# TIDA-01576_ADS8686S_AFE_Pg5-Voltage_Meas.net
KiCad netlist of a schematic drawn in Altium Designer
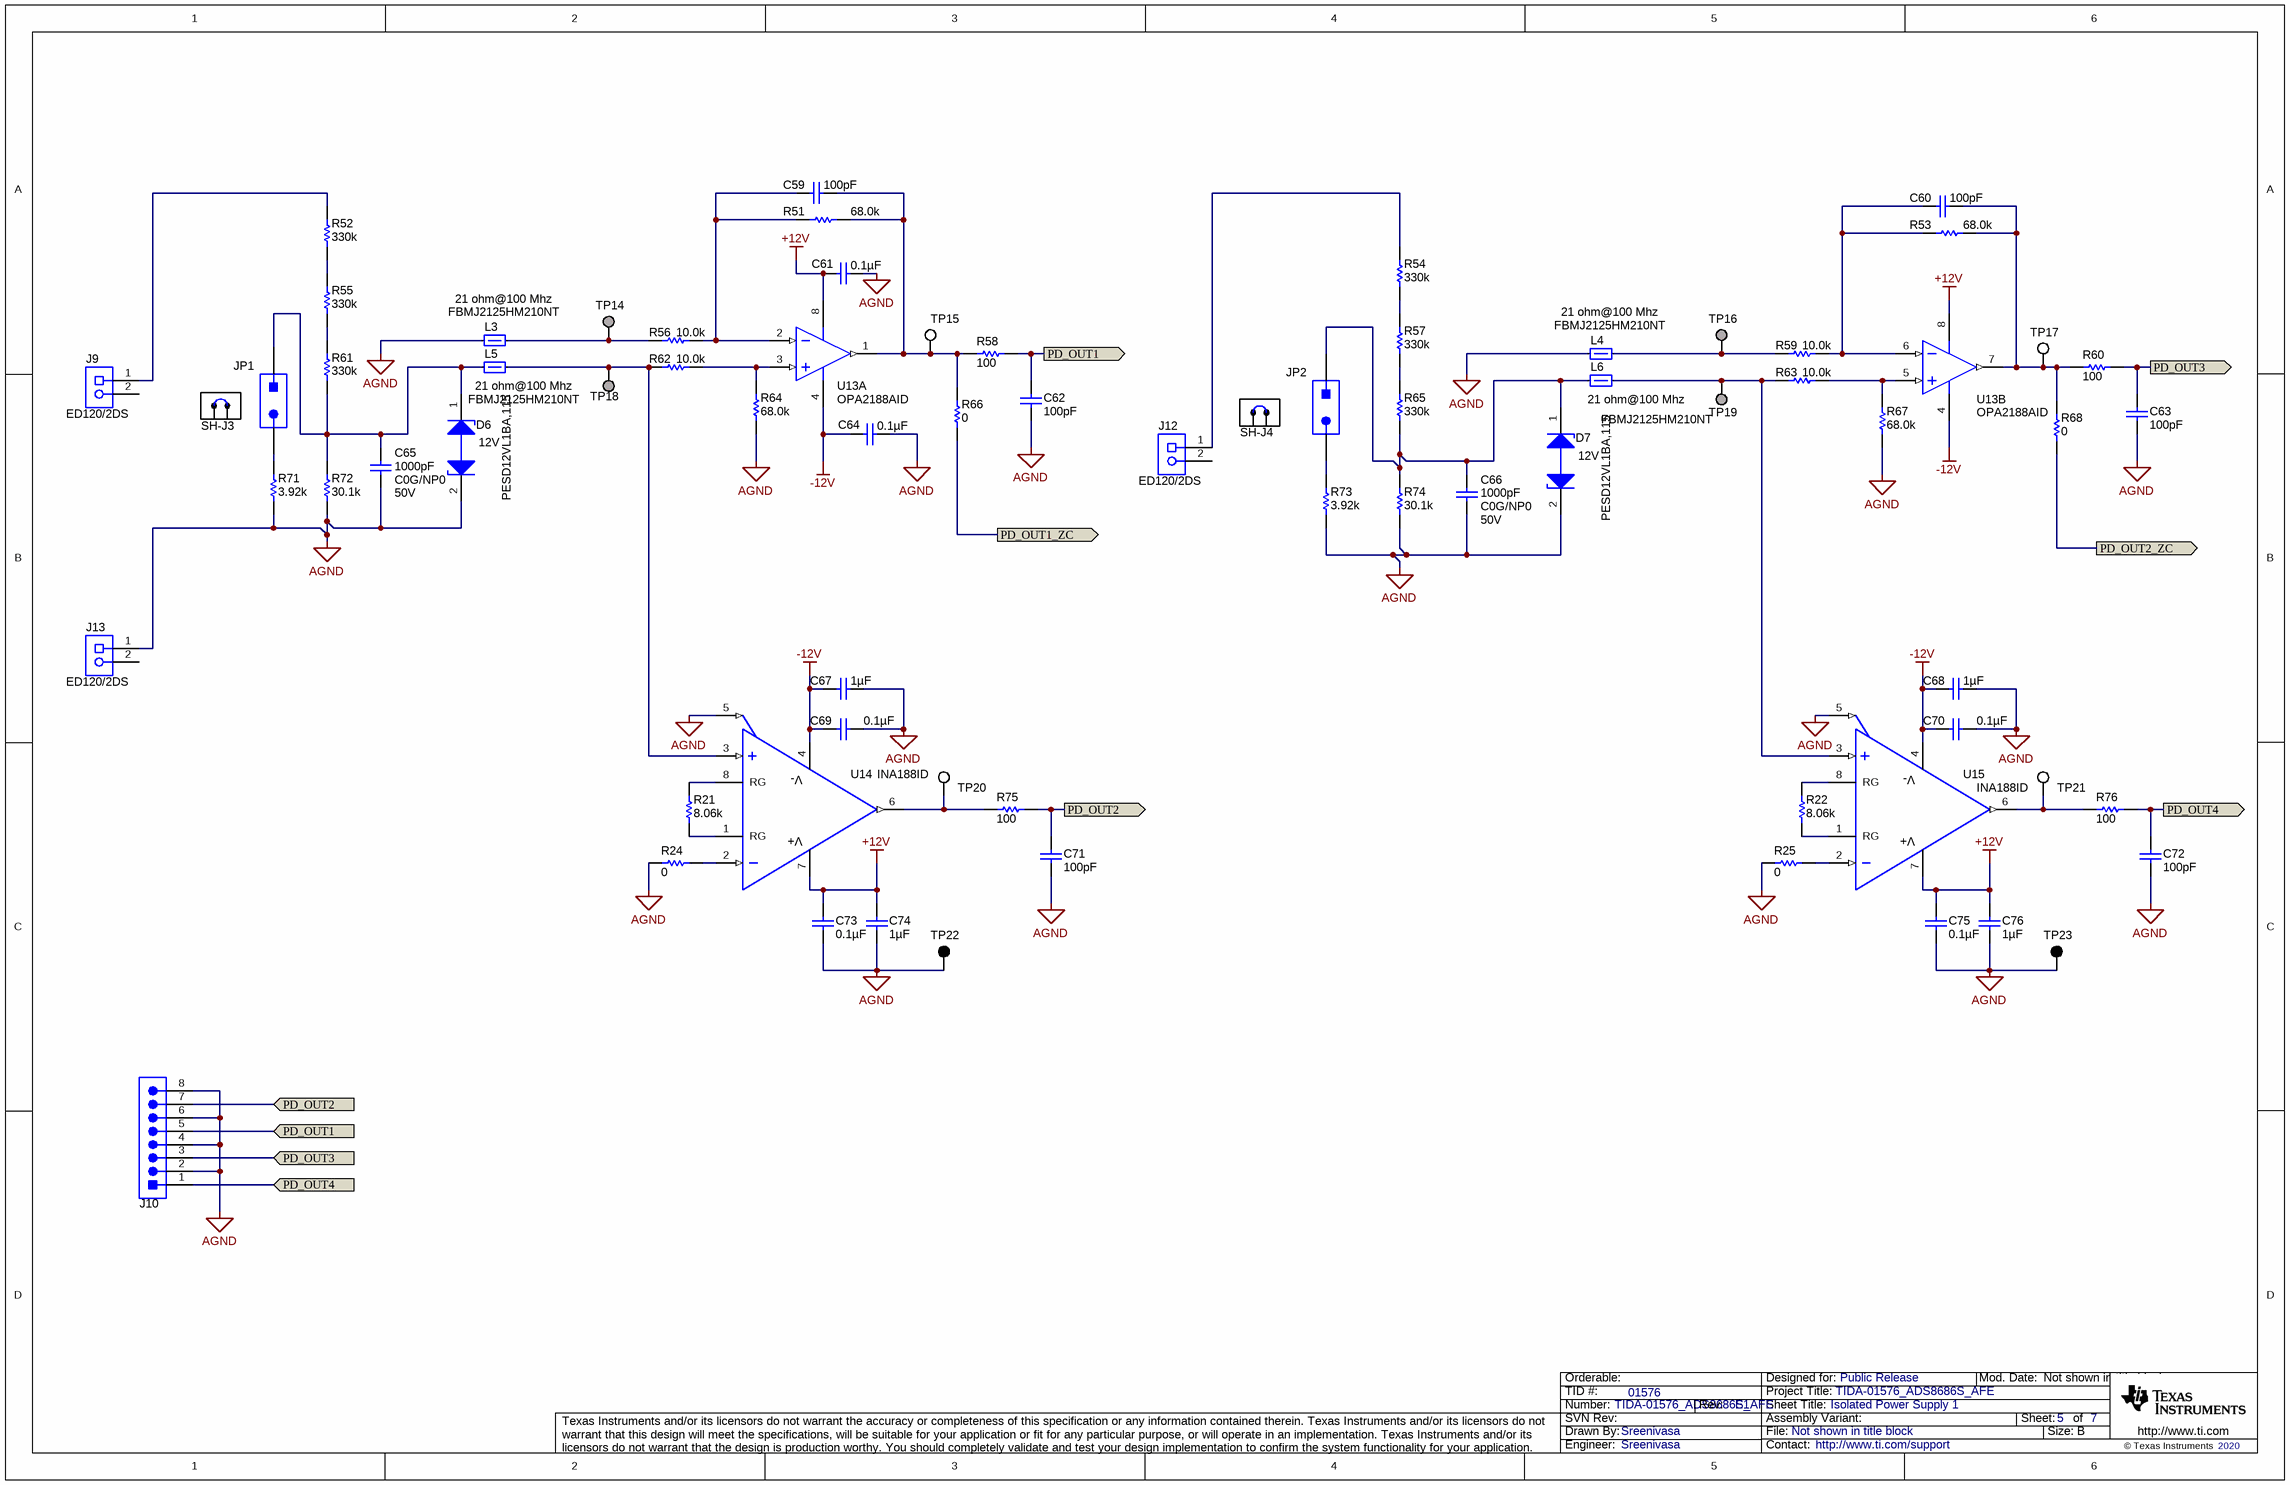
[diagram p0: TIDA-01576_ADS8686S_AFE_Pg5-Voltage Measurement.SchDoc]

(export (version "E")
  (design (tool "Eeschema 10.0.6"))
  (components
    (comp (ref "C59")
      (value "06033C101KAT2A")
      (footprint "0603")
      (description "CAP, CERM, 100pF, 25V, +/-10%, X7R, 0603")
      (fields
        (field (name "VALUEDISPLAYED") "100pF")
        (field (name "MANUFACTURER") "AVX")
        (field (name "PUBLISHER") "Texas Instruments")
      )
      (libsource (lib "Capacitor_Ceramic") (part "06033C101KAT2A"))
    )
    (comp (ref "C60")
      (value "06033C101KAT2A")
      (footprint "0603")
      (description "CAP, CERM, 100pF, 25V, +/-10%, X7R, 0603")
      (fields
        (field (name "VALUEDISPLAYED") "100pF")
        (field (name "MANUFACTURER") "AVX")
        (field (name "PUBLISHER") "Texas Instruments")
      )
      (libsource (lib "Capacitor_Ceramic") (part "06033C101KAT2A"))
    )
    (comp (ref "C61")
      (value "06033C104JAT2A")
      (footprint "0603")
      (description "CAP, CERM, 0.1uF, 25V, +/-5%, X7R, 0603")
      (fields
        (field (name "VALUEDISPLAYED") "0.1µF")
        (field (name "MANUFACTURER") "AVX")
        (field (name "PUBLISHER") "Texas Instruments")
      )
      (libsource (lib "Capacitor_Ceramic") (part "06033C104JAT2A"))
    )
    (comp (ref "C62")
      (value "06033C101KAT2A")
      (footprint "0603")
      (description "CAP, CERM, 100pF, 25V, +/-10%, X7R, 0603")
      (fields
        (field (name "VALUEDISPLAYED") "100pF")
        (field (name "MANUFACTURER") "AVX")
        (field (name "PUBLISHER") "Texas Instruments")
      )
      (libsource (lib "Capacitor_Ceramic") (part "06033C101KAT2A"))
    )
    (comp (ref "C63")
      (value "06033C101KAT2A")
      (footprint "0603")
      (description "CAP, CERM, 100pF, 25V, +/-10%, X7R, 0603")
      (fields
        (field (name "VALUEDISPLAYED") "100pF")
        (field (name "MANUFACTURER") "AVX")
        (field (name "PUBLISHER") "Texas Instruments")
      )
      (libsource (lib "Capacitor_Ceramic") (part "06033C101KAT2A"))
    )
    (comp (ref "C64")
      (value "06033C104JAT2A")
      (footprint "0603")
      (description "CAP, CERM, 0.1uF, 25V, +/-5%, X7R, 0603")
      (fields
        (field (name "VALUEDISPLAYED") "0.1µF")
        (field (name "MANUFACTURER") "AVX")
        (field (name "PUBLISHER") "Texas Instruments")
      )
      (libsource (lib "Capacitor_Ceramic") (part "06033C104JAT2A"))
    )
    (comp (ref "C65")
      (value "C1608C0G1H102J080AA")
      (footprint "0603")
      (description "CAP, CERM, 1000pF, 50V, +/-5%, C0G/NP0, 0603")
      (fields
        (field (name "VALUEDISPLAYED") "1000pF")
        (field (name "MANUFACTURER") "TDK")
        (field (name "VALUE2") "50V")
        (field (name "TEMPCO") "C0G/NP0")
        (field (name "PUBLISHER") "Texas Instruments")
      )
      (libsource (lib "Capacitor_Ceramic") (part "C1608C0G1H102J"))
    )
    (comp (ref "C66")
      (value "C1608C0G1H102J080AA")
      (footprint "0603")
      (description "CAP, CERM, 1000pF, 50V, +/-5%, C0G/NP0, 0603")
      (fields
        (field (name "VALUEDISPLAYED") "1000pF")
        (field (name "MANUFACTURER") "TDK")
        (field (name "VALUE2") "50V")
        (field (name "TEMPCO") "C0G/NP0")
        (field (name "PUBLISHER") "Texas Instruments")
      )
      (libsource (lib "Capacitor_Ceramic") (part "C1608C0G1H102J"))
    )
    (comp (ref "C67")
      (value "GRM188R61C105KA93D")
      (footprint "0603")
      (description "CAP, CERM, 1 µF, 16 V, +/- 10%, X5R, 0603")
      (fields
        (field (name "VALUEDISPLAYED") "1µF")
        (field (name "MANUFACTURER") "Murata")
        (field (name "PUBLISHER") "Texas Instruments")
      )
      (libsource (lib "Capacitor_Ceramic") (part "C1608X5R1C105K"))
    )
    (comp (ref "C68")
      (value "GRM188R61C105KA93D")
      (footprint "0603")
      (description "CAP, CERM, 1 µF, 16 V, +/- 10%, X5R, 0603")
      (fields
        (field (name "VALUEDISPLAYED") "1µF")
        (field (name "MANUFACTURER") "Murata")
        (field (name "PUBLISHER") "Texas Instruments")
      )
      (libsource (lib "Capacitor_Ceramic") (part "C1608X5R1C105K"))
    )
    (comp (ref "C69")
      (value "CGA3E2X8R1E104K080AA")
      (footprint "0603")
      (description "CAP, CERM, 0.1 µF, 25 V, +/- 10%, X8R, AEC-Q200 Grade 0, 0603")
      (fields
        (field (name "VALUEDISPLAYED") "0.1µF")
        (field (name "MANUFACTURER") "TDK")
        (field (name "PUBLISHER") "Texas Instruments")
      )
      (libsource (lib "Capacitor_Ceramic") (part "CGA3E2X8R1E104K080AA"))
    )
    (comp (ref "C70")
      (value "CGA3E2X8R1E104K080AA")
      (footprint "0603")
      (description "CAP, CERM, 0.1 µF, 25 V, +/- 10%, X8R, AEC-Q200 Grade 0, 0603")
      (fields
        (field (name "VALUEDISPLAYED") "0.1µF")
        (field (name "MANUFACTURER") "TDK")
        (field (name "PUBLISHER") "Texas Instruments")
      )
      (libsource (lib "Capacitor_Ceramic") (part "CGA3E2X8R1E104K080AA"))
    )
    (comp (ref "C71")
      (value "06033C101KAT2A")
      (footprint "0603")
      (description "CAP, CERM, 100pF, 25V, +/-10%, X7R, 0603")
      (fields
        (field (name "VALUEDISPLAYED") "100pF")
        (field (name "MANUFACTURER") "AVX")
        (field (name "PUBLISHER") "Texas Instruments")
      )
      (libsource (lib "Capacitor_Ceramic") (part "06033C101KAT2A"))
    )
    (comp (ref "C72")
      (value "06033C101KAT2A")
      (footprint "0603")
      (description "CAP, CERM, 100pF, 25V, +/-10%, X7R, 0603")
      (fields
        (field (name "VALUEDISPLAYED") "100pF")
        (field (name "MANUFACTURER") "AVX")
        (field (name "PUBLISHER") "Texas Instruments")
      )
      (libsource (lib "Capacitor_Ceramic") (part "06033C101KAT2A"))
    )
    (comp (ref "C73")
      (value "CGA3E2X8R1E104K080AA")
      (footprint "0603")
      (description "CAP, CERM, 0.1 µF, 25 V, +/- 10%, X8R, AEC-Q200 Grade 0, 0603")
      (fields
        (field (name "VALUEDISPLAYED") "0.1µF")
        (field (name "MANUFACTURER") "TDK")
        (field (name "PUBLISHER") "Texas Instruments")
      )
      (libsource (lib "Capacitor_Ceramic") (part "CGA3E2X8R1E104K080AA"))
    )
    (comp (ref "C74")
      (value "GRM188R61C105KA93D")
      (footprint "0603")
      (description "CAP, CERM, 1 µF, 16 V, +/- 10%, X5R, 0603")
      (fields
        (field (name "VALUEDISPLAYED") "1µF")
        (field (name "MANUFACTURER") "Murata")
        (field (name "PUBLISHER") "Texas Instruments")
      )
      (libsource (lib "Capacitor_Ceramic") (part "C1608X5R1C105K"))
    )
    (comp (ref "C75")
      (value "CGA3E2X8R1E104K080AA")
      (footprint "0603")
      (description "CAP, CERM, 0.1 µF, 25 V, +/- 10%, X8R, AEC-Q200 Grade 0, 0603")
      (fields
        (field (name "VALUEDISPLAYED") "0.1µF")
        (field (name "MANUFACTURER") "TDK")
        (field (name "PUBLISHER") "Texas Instruments")
      )
      (libsource (lib "Capacitor_Ceramic") (part "CGA3E2X8R1E104K080AA"))
    )
    (comp (ref "C76")
      (value "GRM188R61C105KA93D")
      (footprint "0603")
      (description "CAP, CERM, 1 µF, 16 V, +/- 10%, X5R, 0603")
      (fields
        (field (name "VALUEDISPLAYED") "1µF")
        (field (name "MANUFACTURER") "Murata")
        (field (name "PUBLISHER") "Texas Instruments")
      )
      (libsource (lib "Capacitor_Ceramic") (part "C1608X5R1C105K"))
    )
    (comp (ref "D6")
      (value "12V")
      (footprint "SOD-323")
      (description "TVS DIODE 12VWM 37VC SOD323")
      (fields
        (field (name "PARTNUMBER") "PESD12VL1BA,115")
        (field (name "MANUFACTURER") "NXP Semiconductor")
        (field (name "Comment") "PESD12VL1BA,115")
        (field (name "SYMBOLCREATOR") "x0199378")
      )
      (libsource (lib "PESD3V3L1BA") (part "PESD3V3L1BA"))
    )
    (comp (ref "D7")
      (value "12V")
      (footprint "SOD-323")
      (description "TVS DIODE 12VWM 37VC SOD323")
      (fields
        (field (name "PARTNUMBER") "PESD12VL1BA,115")
        (field (name "MANUFACTURER") "NXP Semiconductor")
        (field (name "Comment") "PESD12VL1BA,115")
        (field (name "SYMBOLCREATOR") "x0199378")
      )
      (libsource (lib "PESD3V3L1BA") (part "PESD3V3L1BA"))
    )
    (comp (ref "J9")
      (value "ED120/2DS")
      (footprint "CONN_ED120-2DS")
      (description "TERMINAL BLOCK 5.08MM VERT 2POS, TH")
      (fields
        (field (name "MANUFACTURER") "On-Shore Technology")
        (field (name "SYMBOLCREATOR") "a0412235")
        (field (name "PUBLISHER") "Texas Instruments")
      )
      (libsource (lib "Connectors") (part "ED120/2DS"))
    )
    (comp (ref "J10")
      (value "1803332")
      (footprint "Phoenix_1803332")
      (description "Header(shrouded), 3.81mm, 8x1, Tin, R/A, TH")
      (fields (field (name "MANUFACTURER") "Phoenix Contact"))
      (libsource (lib "Altium Vault - TI") (part "CMP-0078749-1"))
    )
    (comp (ref "J12")
      (value "ED120/2DS")
      (footprint "CONN_ED120-2DS")
      (description "TERMINAL BLOCK 5.08MM VERT 2POS, TH")
      (fields
        (field (name "MANUFACTURER") "On-Shore Technology")
        (field (name "SYMBOLCREATOR") "a0412235")
        (field (name "PUBLISHER") "Texas Instruments")
      )
      (libsource (lib "Connectors") (part "ED120/2DS"))
    )
    (comp (ref "J13")
      (value "ED120/2DS")
      (footprint "CONN_ED120-2DS")
      (description "TERMINAL BLOCK 5.08MM VERT 2POS, TH")
      (fields
        (field (name "MANUFACTURER") "On-Shore Technology")
        (field (name "SYMBOLCREATOR") "a0412235")
        (field (name "PUBLISHER") "Texas Instruments")
      )
      (libsource (lib "Connectors") (part "ED120/2DS"))
    )
    (comp (ref "JP1")
      (value "5-146280-2")
      (footprint "TSW-102-07-G-S")
      (description "Header, 100mil, 2x1, Gold, TH")
      (fields
        (field (name "MANUFACTURER") "TE Connectivity")
        (field (name "SYMBOLCREATOR") "a0412235")
        (field (name "PUBLISHER") "Texas Instruments")
      )
      (libsource (lib "Connectors_Samtec") (part "TSW-102-07-G-S"))
    )
    (comp (ref "JP2")
      (value "5-146280-2")
      (footprint "TSW-102-07-G-S")
      (description "Header, 100mil, 2x1, Gold, TH")
      (fields
        (field (name "MANUFACTURER") "TE Connectivity")
        (field (name "SYMBOLCREATOR") "a0412235")
        (field (name "PUBLISHER") "Texas Instruments")
      )
      (libsource (lib "Connectors_Samtec") (part "TSW-102-07-G-S"))
    )
    (comp (ref "L3")
      (value "21 ohm@100 Mhz")
      (footprint "0805_HV")
      (description "Ferrite Bead, 21 ohm @ 100 MHz, 6 A, 0805")
      (fields
        (field (name "PARTNUMBER") "FBMJ2125HM210NT")
        (field (name "MANUFACTURER") "Taiyo Yuden")
        (field (name "Comment") "FBMJ2125HM210NT")
        (field (name "PUBLISHER") "Texas Instruments")
      )
      (libsource (lib "FerriteBead") (part "FBMJ2125HM210NT"))
    )
    (comp (ref "L4")
      (value "21 ohm@100 Mhz")
      (footprint "0805_HV")
      (description "Ferrite Bead, 21 ohm @ 100 MHz, 6 A, 0805")
      (fields
        (field (name "PARTNUMBER") "FBMJ2125HM210NT")
        (field (name "MANUFACTURER") "Taiyo Yuden")
        (field (name "Comment") "FBMJ2125HM210NT")
        (field (name "PUBLISHER") "Texas Instruments")
      )
      (libsource (lib "FerriteBead") (part "FBMJ2125HM210NT"))
    )
    (comp (ref "L5")
      (value "21 ohm@100 Mhz")
      (footprint "0805_HV")
      (description "Ferrite Bead, 21 ohm @ 100 MHz, 6 A, 0805")
      (fields
        (field (name "PARTNUMBER") "FBMJ2125HM210NT")
        (field (name "MANUFACTURER") "Taiyo Yuden")
        (field (name "Comment") "FBMJ2125HM210NT")
        (field (name "PUBLISHER") "Texas Instruments")
      )
      (libsource (lib "FerriteBead") (part "FBMJ2125HM210NT"))
    )
    (comp (ref "L6")
      (value "21 ohm@100 Mhz")
      (footprint "0805_HV")
      (description "Ferrite Bead, 21 ohm @ 100 MHz, 6 A, 0805")
      (fields
        (field (name "PARTNUMBER") "FBMJ2125HM210NT")
        (field (name "MANUFACTURER") "Taiyo Yuden")
        (field (name "Comment") "FBMJ2125HM210NT")
        (field (name "PUBLISHER") "Texas Instruments")
      )
      (libsource (lib "FerriteBead") (part "FBMJ2125HM210NT"))
    )
    (comp (ref "R21")
      (value "RG1608P-8061-B-T5")
      (footprint "0603")
      (description "RES, 8.06 k, 0.1%, 0.1 W, 0603")
      (fields
        (field (name "VALUEDISPLAYED") "8.06k")
        (field (name "MANUFACTURER") "Susumu Co Ltd")
        (field (name "PUBLISHER") "Texas Instruments")
      )
      (libsource (lib "Resistor_0603") (part "RG1608P-8061-B-T5"))
    )
    (comp (ref "R22")
      (value "RG1608P-8061-B-T5")
      (footprint "0603")
      (description "RES, 8.06 k, 0.1%, 0.1 W, 0603")
      (fields
        (field (name "VALUEDISPLAYED") "8.06k")
        (field (name "MANUFACTURER") "Susumu Co Ltd")
        (field (name "PUBLISHER") "Texas Instruments")
      )
      (libsource (lib "Resistor_0603") (part "RG1608P-8061-B-T5"))
    )
    (comp (ref "R24")
      (value "RC0603JR-070RL")
      (footprint "0603")
      (description "RES, 0, 5%, 0.1 W, 0603")
      (fields
        (field (name "VALUEDISPLAYED") "0")
        (field (name "MANUFACTURER") "Yageo America")
        (field (name "PUBLISHER") "Texas Instruments")
      )
      (libsource (lib "Resistor_0603") (part "RC0603JR-070RL"))
    )
    (comp (ref "R25")
      (value "RC0603JR-070RL")
      (footprint "0603")
      (description "RES, 0, 5%, 0.1 W, 0603")
      (fields
        (field (name "VALUEDISPLAYED") "0")
        (field (name "MANUFACTURER") "Yageo America")
        (field (name "PUBLISHER") "Texas Instruments")
      )
      (libsource (lib "Resistor_0603") (part "RC0603JR-070RL"))
    )
    (comp (ref "R51")
      (value "RG1608P-683-B-T5")
      (footprint "0603")
      (description "RES, 68.0 k, 0.1%, 0.1 W, 0603")
      (fields
        (field (name "VALUEDISPLAYED") "68.0k")
        (field (name "MANUFACTURER") "Susumu Co Ltd")
        (field (name "PUBLISHER") "Texas Instruments")
      )
      (libsource (lib "Resistor_0603") (part "RG1608P-683-B-T5"))
    )
    (comp (ref "R52")
      (value "TNPV1206330KBEEN")
      (footprint "TNPV1206")
      (description "RES, 330 k, 0.1%, 1 W, 1206")
      (fields
        (field (name "VALUEDISPLAYED") "330k")
        (field (name "MANUFACTURER") "Vishay Draloric")
        (field (name "PUBLISHER") "Texas Instruments")
      )
      (libsource (lib "Resistor_1206") (part "TNPV1206330KBEEN"))
    )
    (comp (ref "R53")
      (value "RG1608P-683-B-T5")
      (footprint "0603")
      (description "RES, 68.0 k, 0.1%, 0.1 W, 0603")
      (fields
        (field (name "VALUEDISPLAYED") "68.0k")
        (field (name "MANUFACTURER") "Susumu Co Ltd")
        (field (name "PUBLISHER") "Texas Instruments")
      )
      (libsource (lib "Resistor_0603") (part "RG1608P-683-B-T5"))
    )
    (comp (ref "R54")
      (value "TNPV1206330KBEEN")
      (footprint "TNPV1206")
      (description "RES, 330 k, 0.1%, 1 W, 1206")
      (fields
        (field (name "VALUEDISPLAYED") "330k")
        (field (name "MANUFACTURER") "Vishay Draloric")
        (field (name "PUBLISHER") "Texas Instruments")
      )
      (libsource (lib "Resistor_1206") (part "TNPV1206330KBEEN"))
    )
    (comp (ref "R55")
      (value "TNPV1206330KBEEN")
      (footprint "TNPV1206")
      (description "RES, 330 k, 0.1%, 1 W, 1206")
      (fields
        (field (name "VALUEDISPLAYED") "330k")
        (field (name "MANUFACTURER") "Vishay Draloric")
        (field (name "PUBLISHER") "Texas Instruments")
      )
      (libsource (lib "Resistor_1206") (part "TNPV1206330KBEEN"))
    )
    (comp (ref "R56")
      (value "RG1608P-103-B-T5")
      (footprint "0603")
      (description "RES, 10.0 k, 0.1%, 0.1 W, 0603")
      (fields
        (field (name "VALUEDISPLAYED") "10.0k")
        (field (name "MANUFACTURER") "Susumu Co Ltd")
        (field (name "PUBLISHER") "Texas Instruments")
      )
      (libsource (lib "Resistor_0603") (part "RG1608P-103-B-T5"))
    )
    (comp (ref "R57")
      (value "TNPV1206330KBEEN")
      (footprint "TNPV1206")
      (description "RES, 330 k, 0.1%, 1 W, 1206")
      (fields
        (field (name "VALUEDISPLAYED") "330k")
        (field (name "MANUFACTURER") "Vishay Draloric")
        (field (name "PUBLISHER") "Texas Instruments")
      )
      (libsource (lib "Resistor_1206") (part "TNPV1206330KBEEN"))
    )
    (comp (ref "R58")
      (value "RG1608P-101-B-T5")
      (footprint "0603")
      (description "RES, 100, 0.1%, 0.1 W, 0603")
      (fields
        (field (name "VALUEDISPLAYED") "100")
        (field (name "MANUFACTURER") "Susumu Co Ltd")
        (field (name "PUBLISHER") "Texas Instruments")
      )
      (libsource (lib "Resistor_0603") (part "RG1608P-101-B-T5"))
    )
    (comp (ref "R59")
      (value "RG1608P-103-B-T5")
      (footprint "0603")
      (description "RES, 10.0 k, 0.1%, 0.1 W, 0603")
      (fields
        (field (name "VALUEDISPLAYED") "10.0k")
        (field (name "MANUFACTURER") "Susumu Co Ltd")
        (field (name "PUBLISHER") "Texas Instruments")
      )
      (libsource (lib "Resistor_0603") (part "RG1608P-103-B-T5"))
    )
    (comp (ref "R60")
      (value "RG1608P-101-B-T5")
      (footprint "0603")
      (description "RES, 100, 0.1%, 0.1 W, 0603")
      (fields
        (field (name "VALUEDISPLAYED") "100")
        (field (name "MANUFACTURER") "Susumu Co Ltd")
        (field (name "PUBLISHER") "Texas Instruments")
      )
      (libsource (lib "Resistor_0603") (part "RG1608P-101-B-T5"))
    )
    (comp (ref "R61")
      (value "TNPV1206330KBEEN")
      (footprint "TNPV1206")
      (description "RES, 330 k, 0.1%, 1 W, 1206")
      (fields
        (field (name "VALUEDISPLAYED") "330k")
        (field (name "MANUFACTURER") "Vishay Draloric")
        (field (name "PUBLISHER") "Texas Instruments")
      )
      (libsource (lib "Resistor_1206") (part "TNPV1206330KBEEN"))
    )
    (comp (ref "R62")
      (value "RG1608P-103-B-T5")
      (footprint "0603")
      (description "RES, 10.0 k, 0.1%, 0.1 W, 0603")
      (fields
        (field (name "VALUEDISPLAYED") "10.0k")
        (field (name "MANUFACTURER") "Susumu Co Ltd")
        (field (name "PUBLISHER") "Texas Instruments")
      )
      (libsource (lib "Resistor_0603") (part "RG1608P-103-B-T5"))
    )
    (comp (ref "R63")
      (value "RG1608P-103-B-T5")
      (footprint "0603")
      (description "RES, 10.0 k, 0.1%, 0.1 W, 0603")
      (fields
        (field (name "VALUEDISPLAYED") "10.0k")
        (field (name "MANUFACTURER") "Susumu Co Ltd")
        (field (name "PUBLISHER") "Texas Instruments")
      )
      (libsource (lib "Resistor_0603") (part "RG1608P-103-B-T5"))
    )
    (comp (ref "R64")
      (value "RG1608P-683-B-T5")
      (footprint "0603")
      (description "RES, 68.0 k, 0.1%, 0.1 W, 0603")
      (fields
        (field (name "VALUEDISPLAYED") "68.0k")
        (field (name "MANUFACTURER") "Susumu Co Ltd")
        (field (name "PUBLISHER") "Texas Instruments")
      )
      (libsource (lib "Resistor_0603") (part "RG1608P-683-B-T5"))
    )
    (comp (ref "R65")
      (value "TNPV1206330KBEEN")
      (footprint "TNPV1206")
      (description "RES, 330 k, 0.1%, 1 W, 1206")
      (fields
        (field (name "VALUEDISPLAYED") "330k")
        (field (name "MANUFACTURER") "Vishay Draloric")
        (field (name "PUBLISHER") "Texas Instruments")
      )
      (libsource (lib "Resistor_1206") (part "TNPV1206330KBEEN"))
    )
    (comp (ref "R66")
      (value "RC0603JR-070RL")
      (footprint "0603")
      (description "RES, 0, 5%, 0.1 W, 0603")
      (fields
        (field (name "VALUEDISPLAYED") "0")
        (field (name "MANUFACTURER") "Yageo America")
        (field (name "PUBLISHER") "Texas Instruments")
      )
      (libsource (lib "Resistor_0603") (part "RC0603JR-070RL"))
    )
    (comp (ref "R67")
      (value "RG1608P-683-B-T5")
      (footprint "0603")
      (description "RES, 68.0 k, 0.1%, 0.1 W, 0603")
      (fields
        (field (name "VALUEDISPLAYED") "68.0k")
        (field (name "MANUFACTURER") "Susumu Co Ltd")
        (field (name "PUBLISHER") "Texas Instruments")
      )
      (libsource (lib "Resistor_0603") (part "RG1608P-683-B-T5"))
    )
    (comp (ref "R68")
      (value "RC0603JR-070RL")
      (footprint "0603")
      (description "RES, 0, 5%, 0.1 W, 0603")
      (fields
        (field (name "VALUEDISPLAYED") "0")
        (field (name "MANUFACTURER") "Yageo America")
        (field (name "PUBLISHER") "Texas Instruments")
      )
      (libsource (lib "Resistor_0603") (part "RC0603JR-070RL"))
    )
    (comp (ref "R71")
      (value "RG1608P-3921-B-T5")
      (footprint "0603")
      (description "RES, 3.92 k, 0.1%, 0.1 W, 0603")
      (fields
        (field (name "VALUEDISPLAYED") "3.92k")
        (field (name "MANUFACTURER") "Susumu Co Ltd")
        (field (name "PUBLISHER") "Texas Instruments")
      )
      (libsource (lib "Resistor_0603") (part "RG1608P-3921-B-T5"))
    )
    (comp (ref "R72")
      (value "RG1608P-3012-B-T5")
      (footprint "0603")
      (description "RES, 30.1 k, 0.1%, 0.1 W, 0603")
      (fields
        (field (name "VALUEDISPLAYED") "30.1k")
        (field (name "MANUFACTURER") "Susumu Co Ltd")
        (field (name "PUBLISHER") "Texas Instruments")
      )
      (libsource (lib "Resistor_0603") (part "RG1608P-3012-B-T5"))
    )
    (comp (ref "R73")
      (value "RG1608P-3921-B-T5")
      (footprint "0603")
      (description "RES, 3.92 k, 0.1%, 0.1 W, 0603")
      (fields
        (field (name "VALUEDISPLAYED") "3.92k")
        (field (name "MANUFACTURER") "Susumu Co Ltd")
        (field (name "PUBLISHER") "Texas Instruments")
      )
      (libsource (lib "Resistor_0603") (part "RG1608P-3921-B-T5"))
    )
    (comp (ref "R74")
      (value "RG1608P-3012-B-T5")
      (footprint "0603")
      (description "RES, 30.1 k, 0.1%, 0.1 W, 0603")
      (fields
        (field (name "VALUEDISPLAYED") "30.1k")
        (field (name "MANUFACTURER") "Susumu Co Ltd")
        (field (name "PUBLISHER") "Texas Instruments")
      )
      (libsource (lib "Resistor_0603") (part "RG1608P-3012-B-T5"))
    )
    (comp (ref "R75")
      (value "RG1608P-101-B-T5")
      (footprint "0603")
      (description "RES, 100, 0.1%, 0.1 W, 0603")
      (fields
        (field (name "VALUEDISPLAYED") "100")
        (field (name "MANUFACTURER") "Susumu Co Ltd")
        (field (name "PUBLISHER") "Texas Instruments")
      )
      (libsource (lib "Resistor_0603") (part "RG1608P-101-B-T5"))
    )
    (comp (ref "R76")
      (value "RG1608P-101-B-T5")
      (footprint "0603")
      (description "RES, 100, 0.1%, 0.1 W, 0603")
      (fields
        (field (name "VALUEDISPLAYED") "100")
        (field (name "MANUFACTURER") "Susumu Co Ltd")
        (field (name "PUBLISHER") "Texas Instruments")
      )
      (libsource (lib "Resistor_0603") (part "RG1608P-101-B-T5"))
    )
    (comp (ref "SH-J3")
      (value "881545-2")
      (footprint "TE_881545-2")
      (description "Shunt, 100mil, Gold plated, Black")
      (fields (field (name "MANUFACTURER") "TE Connectivity") (field (name "PUBLISHER") "Texas Instruments"))
      (libsource (lib "Hardware") (part "881545-2"))
    )
    (comp (ref "SH-J4")
      (value "881545-2")
      (footprint "TE_881545-2")
      (description "Shunt, 100mil, Gold plated, Black")
      (fields (field (name "MANUFACTURER") "TE Connectivity") (field (name "PUBLISHER") "Texas Instruments"))
      (libsource (lib "Hardware") (part "881545-2"))
    )
    (comp (ref "TP14")
      (value "Suggest using a net name here")
      (footprint "Keystone1573-2")
      (description "Terminal, Turret, TH, Double")
      (fields
        (field (name "PARTNUMBER") "1573-2")
        (field (name "MANUFACTURER") "Keystone")
        (field (name "PUBLISHER") "Texas Instruments")
      )
      (libsource (lib "Connectors_Keystone") (part "1573-2"))
    )
    (comp (ref "TP15")
      (value "5002")
      (footprint "Keystone5002")
      (description "Test Point, Miniature, White, TH")
      (fields (field (name "MANUFACTURER") "Keystone") (field (name "PUBLISHER") "Texas Instruments"))
      (libsource (lib "Connectors_Keystone") (part "5002"))
    )
    (comp (ref "TP16")
      (value "Suggest using a net name here")
      (footprint "Keystone1573-2")
      (description "Terminal, Turret, TH, Double")
      (fields
        (field (name "PARTNUMBER") "1573-2")
        (field (name "MANUFACTURER") "Keystone")
        (field (name "PUBLISHER") "Texas Instruments")
      )
      (libsource (lib "Connectors_Keystone") (part "1573-2"))
    )
    (comp (ref "TP17")
      (value "5002")
      (footprint "Keystone5002")
      (description "Test Point, Miniature, White, TH")
      (fields (field (name "MANUFACTURER") "Keystone") (field (name "PUBLISHER") "Texas Instruments"))
      (libsource (lib "Connectors_Keystone") (part "5002"))
    )
    (comp (ref "TP18")
      (value "Suggest using a net name here")
      (footprint "Keystone1573-2")
      (description "Terminal, Turret, TH, Double")
      (fields
        (field (name "PARTNUMBER") "1573-2")
        (field (name "MANUFACTURER") "Keystone")
        (field (name "PUBLISHER") "Texas Instruments")
      )
      (libsource (lib "Connectors_Keystone") (part "1573-2"))
    )
    (comp (ref "TP19")
      (value "Suggest using a net name here")
      (footprint "Keystone1573-2")
      (description "Terminal, Turret, TH, Double")
      (fields
        (field (name "PARTNUMBER") "1573-2")
        (field (name "MANUFACTURER") "Keystone")
        (field (name "PUBLISHER") "Texas Instruments")
      )
      (libsource (lib "Connectors_Keystone") (part "1573-2"))
    )
    (comp (ref "TP20")
      (value "5002")
      (footprint "Keystone5002")
      (description "Test Point, Miniature, White, TH")
      (fields (field (name "MANUFACTURER") "Keystone") (field (name "PUBLISHER") "Texas Instruments"))
      (libsource (lib "Connectors_Keystone") (part "5002"))
    )
    (comp (ref "TP21")
      (value "5002")
      (footprint "Keystone5002")
      (description "Test Point, Miniature, White, TH")
      (fields (field (name "MANUFACTURER") "Keystone") (field (name "PUBLISHER") "Texas Instruments"))
      (libsource (lib "Connectors_Keystone") (part "5002"))
    )
    (comp (ref "TP22")
      (value "5001")
      (footprint "Keystone5001")
      (description "Test Point, Miniature, Black, TH")
      (fields (field (name "MANUFACTURER") "Keystone") (field (name "PUBLISHER") "Texas Instruments"))
      (libsource (lib "Connectors_Keystone") (part "5001"))
    )
    (comp (ref "TP23")
      (value "5001")
      (footprint "Keystone5001")
      (description "Test Point, Miniature, Black, TH")
      (fields (field (name "MANUFACTURER") "Keystone") (field (name "PUBLISHER") "Texas Instruments"))
      (libsource (lib "Connectors_Keystone") (part "5001"))
    )
    (comp (ref "U13")
      (value "OPA2188AID")
      (footprint "D0008A_N")
      (fields
        (field (name "MANUFACTURER") "Texas Instruments")
        (field (name "ALTERNATE PARTNUMBER") "Equivalent")
      )
      (libsource (lib "TI Amplifiers and Linear Operational Amplifier Precision Amplifier Part One") (part "OPA2188AID"))
    )
    (comp (ref "U14")
      (value "INA188ID")
      (footprint "D0008A_N")
      (description "INA188 Precision, Zero-Drift, Rail-to-Rail Out, High Voltage Instrumentation Amplifier, D0008A")
      (fields
        (field (name "MANUFACTURER") "Texas Instruments")
        (field (name "SYMBOLCREATOR") "Altium")
        (field (name "PUBLISHER") "Texas Instruments")
      )
      (libsource (lib "TI_Pre_RTM") (part "INA188D"))
    )
    (comp (ref "U15")
      (value "INA188ID")
      (footprint "D0008A_N")
      (description "INA188 Precision, Zero-Drift, Rail-to-Rail Out, High Voltage Instrumentation Amplifier, D0008A")
      (fields
        (field (name "MANUFACTURER") "Texas Instruments")
        (field (name "SYMBOLCREATOR") "Altium")
        (field (name "PUBLISHER") "Texas Instruments")
      )
      (libsource (lib "TI_Pre_RTM") (part "INA188D"))
    )
  )
  (nets
    (net (code "1") (name "+12V") (class "Default")
      (node (ref "C61") (pin "2") (pinfunction "2_2") (pintype "passive"))
      (node (ref "C73") (pin "1") (pinfunction "1_1") (pintype "passive"))
      (node (ref "C74") (pin "1") (pinfunction "1_1") (pintype "passive"))
      (node (ref "C75") (pin "1") (pinfunction "1_1") (pintype "passive"))
      (node (ref "C76") (pin "1") (pinfunction "1_1") (pintype "passive"))
      (node (ref "U13") (pin "8") (pinfunction "V+_8") (pintype "power_in"))
      (node (ref "U14") (pin "7") (pinfunction "V+_7") (pintype "power_in"))
      (node (ref "U15") (pin "7") (pinfunction "V+_7") (pintype "power_in"))
    )
    (net (code "2") (name "-12V") (class "Default")
      (node (ref "C64") (pin "2") (pinfunction "2_2") (pintype "passive"))
      (node (ref "C67") (pin "1") (pinfunction "1_1") (pintype "passive"))
      (node (ref "C68") (pin "1") (pinfunction "1_1") (pintype "passive"))
      (node (ref "C69") (pin "1") (pinfunction "1_1") (pintype "passive"))
      (node (ref "C70") (pin "1") (pinfunction "1_1") (pintype "passive"))
      (node (ref "U13") (pin "4") (pinfunction "V-_4") (pintype "power_in"))
      (node (ref "U14") (pin "4") (pinfunction "V-_4") (pintype "power_in"))
      (node (ref "U15") (pin "4") (pinfunction "V-_4") (pintype "power_in"))
    )
    (net (code "3") (name "/PD_OUT1") (class "Default")
      (node (ref "C62") (pin "1") (pinfunction "1_1") (pintype "passive"))
      (node (ref "J10") (pin "5") (pinfunction "5_5") (pintype "passive"))
      (node (ref "R58") (pin "2") (pinfunction "2_2") (pintype "passive"))
    )
    (net (code "4") (name "/PD_OUT1_ZC") (class "Default")
      (node (ref "R66") (pin "1") (pinfunction "1_1") (pintype "passive"))
    )
    (net (code "5") (name "/PD_OUT2") (class "Default")
      (node (ref "C71") (pin "1") (pinfunction "1_1") (pintype "passive"))
      (node (ref "J10") (pin "7") (pinfunction "7_7") (pintype "passive"))
      (node (ref "R75") (pin "2") (pinfunction "2_2") (pintype "passive"))
    )
    (net (code "6") (name "/PD_OUT2_ZC") (class "Default")
      (node (ref "R68") (pin "1") (pinfunction "1_1") (pintype "passive"))
    )
    (net (code "7") (name "/PD_OUT3") (class "Default")
      (node (ref "C63") (pin "1") (pinfunction "1_1") (pintype "passive"))
      (node (ref "J10") (pin "3") (pinfunction "3_3") (pintype "passive"))
      (node (ref "R60") (pin "2") (pinfunction "2_2") (pintype "passive"))
    )
    (net (code "8") (name "/PD_OUT4") (class "Default")
      (node (ref "C72") (pin "1") (pinfunction "1_1") (pintype "passive"))
      (node (ref "J10") (pin "1") (pinfunction "1_1") (pintype "passive"))
      (node (ref "R76") (pin "2") (pinfunction "2_2") (pintype "passive"))
    )
    (net (code "9") (name "AGND") (class "Default")
      (node (ref "C61") (pin "1") (pinfunction "1_1") (pintype "passive"))
      (node (ref "C62") (pin "2") (pinfunction "2_2") (pintype "passive"))
      (node (ref "C63") (pin "2") (pinfunction "2_2") (pintype "passive"))
      (node (ref "C64") (pin "1") (pinfunction "1_1") (pintype "passive"))
      (node (ref "C65") (pin "1") (pinfunction "1_1") (pintype "passive"))
      (node (ref "C66") (pin "1") (pinfunction "1_1") (pintype "passive"))
      (node (ref "C67") (pin "2") (pinfunction "2_2") (pintype "passive"))
      (node (ref "C68") (pin "2") (pinfunction "2_2") (pintype "passive"))
      (node (ref "C69") (pin "2") (pinfunction "2_2") (pintype "passive"))
      (node (ref "C70") (pin "2") (pinfunction "2_2") (pintype "passive"))
      (node (ref "C71") (pin "2") (pinfunction "2_2") (pintype "passive"))
      (node (ref "C72") (pin "2") (pinfunction "2_2") (pintype "passive"))
      (node (ref "C73") (pin "2") (pinfunction "2_2") (pintype "passive"))
      (node (ref "C74") (pin "2") (pinfunction "2_2") (pintype "passive"))
      (node (ref "C75") (pin "2") (pinfunction "2_2") (pintype "passive"))
      (node (ref "C76") (pin "2") (pinfunction "2_2") (pintype "passive"))
      (node (ref "D6") (pin "2") (pinfunction "K_2") (pintype "passive"))
      (node (ref "D7") (pin "2") (pinfunction "K_2") (pintype "passive"))
      (node (ref "J10") (pin "2") (pinfunction "2_2") (pintype "passive"))
      (node (ref "J10") (pin "4") (pinfunction "4_4") (pintype "passive"))
      (node (ref "J10") (pin "6") (pinfunction "6_6") (pintype "passive"))
      (node (ref "J10") (pin "8") (pinfunction "8_8") (pintype "passive"))
      (node (ref "J13") (pin "1") (pinfunction "1_1") (pintype "passive"))
      (node (ref "L3") (pin "1") (pinfunction "1_1") (pintype "passive"))
      (node (ref "L4") (pin "1") (pinfunction "1_1") (pintype "passive"))
      (node (ref "R24") (pin "2") (pinfunction "2_2") (pintype "passive"))
      (node (ref "R25") (pin "2") (pinfunction "2_2") (pintype "passive"))
      (node (ref "R64") (pin "1") (pinfunction "1_1") (pintype "passive"))
      (node (ref "R67") (pin "1") (pinfunction "1_1") (pintype "passive"))
      (node (ref "R71") (pin "1") (pinfunction "1_1") (pintype "passive"))
      (node (ref "R72") (pin "1") (pinfunction "1_1") (pintype "passive"))
      (node (ref "R73") (pin "1") (pinfunction "1_1") (pintype "passive"))
      (node (ref "R74") (pin "1") (pinfunction "1_1") (pintype "passive"))
      (node (ref "TP22") (pin "1") (pintype "passive"))
      (node (ref "TP23") (pin "1") (pintype "passive"))
      (node (ref "U14") (pin "5") (pinfunction "REF_5") (pintype "input"))
      (node (ref "U15") (pin "5") (pinfunction "REF_5") (pintype "input"))
    )
    (net (code "10") (name "Net-(C65-Pad2)") (class "Default")
      (node (ref "C65") (pin "2") (pinfunction "2_2") (pintype "passive"))
      (node (ref "D6") (pin "1") (pinfunction "K_1") (pintype "passive"))
      (node (ref "JP1") (pin "1") (pinfunction "1_1") (pintype "passive"))
      (node (ref "L5") (pin "1") (pinfunction "1_1") (pintype "passive"))
      (node (ref "R61") (pin "1") (pinfunction "1_1") (pintype "passive"))
      (node (ref "R72") (pin "2") (pinfunction "2_2") (pintype "passive"))
    )
    (net (code "11") (name "Net-(C66-Pad2)") (class "Default")
      (node (ref "C66") (pin "2") (pinfunction "2_2") (pintype "passive"))
      (node (ref "D7") (pin "1") (pinfunction "K_1") (pintype "passive"))
      (node (ref "JP2") (pin "1") (pinfunction "1_1") (pintype "passive"))
      (node (ref "L6") (pin "1") (pinfunction "1_1") (pintype "passive"))
      (node (ref "R65") (pin "1") (pinfunction "1_1") (pintype "passive"))
      (node (ref "R74") (pin "2") (pinfunction "2_2") (pintype "passive"))
    )
    (net (code "12") (name "Net-(J9-Pad1)") (class "Default")
      (node (ref "J9") (pin "1") (pinfunction "1_1") (pintype "passive"))
      (node (ref "R52") (pin "2") (pinfunction "2_2") (pintype "passive"))
    )
    (net (code "13") (name "Net-(J12-Pad1)") (class "Default")
      (node (ref "J12") (pin "1") (pinfunction "1_1") (pintype "passive"))
      (node (ref "R54") (pin "2") (pinfunction "2_2") (pintype "passive"))
    )
    (net (code "14") (name "Net-(JP1-Pad2)") (class "Default")
      (node (ref "JP1") (pin "2") (pinfunction "2_2") (pintype "passive"))
      (node (ref "R71") (pin "2") (pinfunction "2_2") (pintype "passive"))
    )
    (net (code "15") (name "Net-(JP2-Pad2)") (class "Default")
      (node (ref "JP2") (pin "2") (pinfunction "2_2") (pintype "passive"))
      (node (ref "R73") (pin "2") (pinfunction "2_2") (pintype "passive"))
    )
    (net (code "16") (name "Net-(L3-Pad2)") (class "Default")
      (node (ref "L3") (pin "2") (pinfunction "2_2") (pintype "passive"))
      (node (ref "R56") (pin "2") (pinfunction "2_2") (pintype "passive"))
      (node (ref "TP14") (pin "1") (pintype "passive"))
    )
    (net (code "17") (name "Net-(L4-Pad2)") (class "Default")
      (node (ref "L4") (pin "2") (pinfunction "2_2") (pintype "passive"))
      (node (ref "R59") (pin "2") (pinfunction "2_2") (pintype "passive"))
      (node (ref "TP16") (pin "1") (pintype "passive"))
    )
    (net (code "18") (name "Net-(R21-Pad1)") (class "Default")
      (node (ref "R21") (pin "1") (pinfunction "1_1") (pintype "passive"))
      (node (ref "U14") (pin "1") (pinfunction "RG_1") (pintype "passive"))
    )
    (net (code "19") (name "Net-(R21-Pad2)") (class "Default")
      (node (ref "R21") (pin "2") (pinfunction "2_2") (pintype "passive"))
      (node (ref "U14") (pin "8") (pinfunction "RG_8") (pintype "passive"))
    )
    (net (code "20") (name "Net-(R22-Pad1)") (class "Default")
      (node (ref "R22") (pin "1") (pinfunction "1_1") (pintype "passive"))
      (node (ref "U15") (pin "1") (pinfunction "RG_1") (pintype "passive"))
    )
    (net (code "21") (name "Net-(R22-Pad2)") (class "Default")
      (node (ref "R22") (pin "2") (pinfunction "2_2") (pintype "passive"))
      (node (ref "U15") (pin "8") (pinfunction "RG_8") (pintype "passive"))
    )
    (net (code "22") (name "Net-(R52-Pad1)") (class "Default")
      (node (ref "R52") (pin "1") (pinfunction "1_1") (pintype "passive"))
      (node (ref "R55") (pin "2") (pinfunction "2_2") (pintype "passive"))
    )
    (net (code "23") (name "Net-(R54-Pad1)") (class "Default")
      (node (ref "R54") (pin "1") (pinfunction "1_1") (pintype "passive"))
      (node (ref "R57") (pin "2") (pinfunction "2_2") (pintype "passive"))
    )
    (net (code "24") (name "Net-(R55-Pad1)") (class "Default")
      (node (ref "R55") (pin "1") (pinfunction "1_1") (pintype "passive"))
      (node (ref "R61") (pin "2") (pinfunction "2_2") (pintype "passive"))
    )
    (net (code "25") (name "Net-(R57-Pad1)") (class "Default")
      (node (ref "R57") (pin "1") (pinfunction "1_1") (pintype "passive"))
      (node (ref "R65") (pin "2") (pinfunction "2_2") (pintype "passive"))
    )
    (net (code "26") (name "Net-(U13A-IN_A+)") (class "Default")
      (node (ref "R62") (pin "1") (pinfunction "1_1") (pintype "passive"))
      (node (ref "R64") (pin "2") (pinfunction "2_2") (pintype "passive"))
      (node (ref "U13") (pin "3") (pinfunction "IN_A+_3") (pintype "input"))
    )
    (net (code "27") (name "Net-(U13A-IN_A-)") (class "Default")
      (node (ref "C59") (pin "1") (pinfunction "1_1") (pintype "passive"))
      (node (ref "R51") (pin "2") (pinfunction "2_2") (pintype "passive"))
      (node (ref "R56") (pin "1") (pinfunction "1_1") (pintype "passive"))
      (node (ref "U13") (pin "2") (pinfunction "IN_A-_2") (pintype "input"))
    )
    (net (code "28") (name "Net-(U13A-OUT_A)") (class "Default")
      (node (ref "C59") (pin "2") (pinfunction "2_2") (pintype "passive"))
      (node (ref "R51") (pin "1") (pinfunction "1_1") (pintype "passive"))
      (node (ref "R58") (pin "1") (pinfunction "1_1") (pintype "passive"))
      (node (ref "R66") (pin "2") (pinfunction "2_2") (pintype "passive"))
      (node (ref "TP15") (pin "1") (pintype "passive"))
      (node (ref "U13") (pin "1") (pinfunction "OUT_A_1") (pintype "output"))
    )
    (net (code "29") (name "Net-(U13B-IN_B+)") (class "Default")
      (node (ref "R63") (pin "1") (pinfunction "1_1") (pintype "passive"))
      (node (ref "R67") (pin "2") (pinfunction "2_2") (pintype "passive"))
      (node (ref "U13") (pin "5") (pinfunction "IN_B+_5") (pintype "input"))
    )
    (net (code "30") (name "Net-(U13B-IN_B-)") (class "Default")
      (node (ref "C60") (pin "1") (pinfunction "1_1") (pintype "passive"))
      (node (ref "R53") (pin "2") (pinfunction "2_2") (pintype "passive"))
      (node (ref "R59") (pin "1") (pinfunction "1_1") (pintype "passive"))
      (node (ref "U13") (pin "6") (pinfunction "IN_B-_6") (pintype "input"))
    )
    (net (code "31") (name "Net-(U13B-OUT_B)") (class "Default")
      (node (ref "C60") (pin "2") (pinfunction "2_2") (pintype "passive"))
      (node (ref "R53") (pin "1") (pinfunction "1_1") (pintype "passive"))
      (node (ref "R60") (pin "1") (pinfunction "1_1") (pintype "passive"))
      (node (ref "R68") (pin "2") (pinfunction "2_2") (pintype "passive"))
      (node (ref "TP17") (pin "1") (pintype "passive"))
      (node (ref "U13") (pin "7") (pinfunction "OUT_B_7") (pintype "output"))
    )
    (net (code "32") (name "Net-(U14-IN+)") (class "Default")
      (node (ref "L5") (pin "2") (pinfunction "2_2") (pintype "passive"))
      (node (ref "R62") (pin "2") (pinfunction "2_2") (pintype "passive"))
      (node (ref "TP18") (pin "1") (pintype "passive"))
      (node (ref "U14") (pin "3") (pinfunction "IN+_3") (pintype "input"))
    )
    (net (code "33") (name "Net-(U14-IN-)") (class "Default")
      (node (ref "R24") (pin "1") (pinfunction "1_1") (pintype "passive"))
      (node (ref "U14") (pin "2") (pinfunction "IN-_2") (pintype "input"))
    )
    (net (code "34") (name "Net-(U14-OUT)") (class "Default")
      (node (ref "R75") (pin "1") (pinfunction "1_1") (pintype "passive"))
      (node (ref "TP20") (pin "1") (pintype "passive"))
      (node (ref "U14") (pin "6") (pinfunction "OUT_6") (pintype "output"))
    )
    (net (code "35") (name "Net-(U15-IN+)") (class "Default")
      (node (ref "L6") (pin "2") (pinfunction "2_2") (pintype "passive"))
      (node (ref "R63") (pin "2") (pinfunction "2_2") (pintype "passive"))
      (node (ref "TP19") (pin "1") (pintype "passive"))
      (node (ref "U15") (pin "3") (pinfunction "IN+_3") (pintype "input"))
    )
    (net (code "36") (name "Net-(U15-IN-)") (class "Default")
      (node (ref "R25") (pin "1") (pinfunction "1_1") (pintype "passive"))
      (node (ref "U15") (pin "2") (pinfunction "IN-_2") (pintype "input"))
    )
    (net (code "37") (name "Net-(U15-OUT)") (class "Default")
      (node (ref "R76") (pin "1") (pinfunction "1_1") (pintype "passive"))
      (node (ref "TP21") (pin "1") (pintype "passive"))
      (node (ref "U15") (pin "6") (pinfunction "OUT_6") (pintype "output"))
    )
    (net (code "38") (name "unconnected-(J9-Pad2)") (class "Default")
      (node (ref "J9") (pin "2") (pinfunction "2_2") (pintype "passive"))
    )
    (net (code "39") (name "unconnected-(J12-Pad2)") (class "Default")
      (node (ref "J12") (pin "2") (pinfunction "2_2") (pintype "passive"))
    )
    (net (code "40") (name "unconnected-(J13-Pad2)") (class "Default")
      (node (ref "J13") (pin "2") (pinfunction "2_2") (pintype "passive"))
    )
  )
)
